# Microcontroller_board_Photodiode_plate.net
KiCad netlist of a schematic drawn in EasyEDA
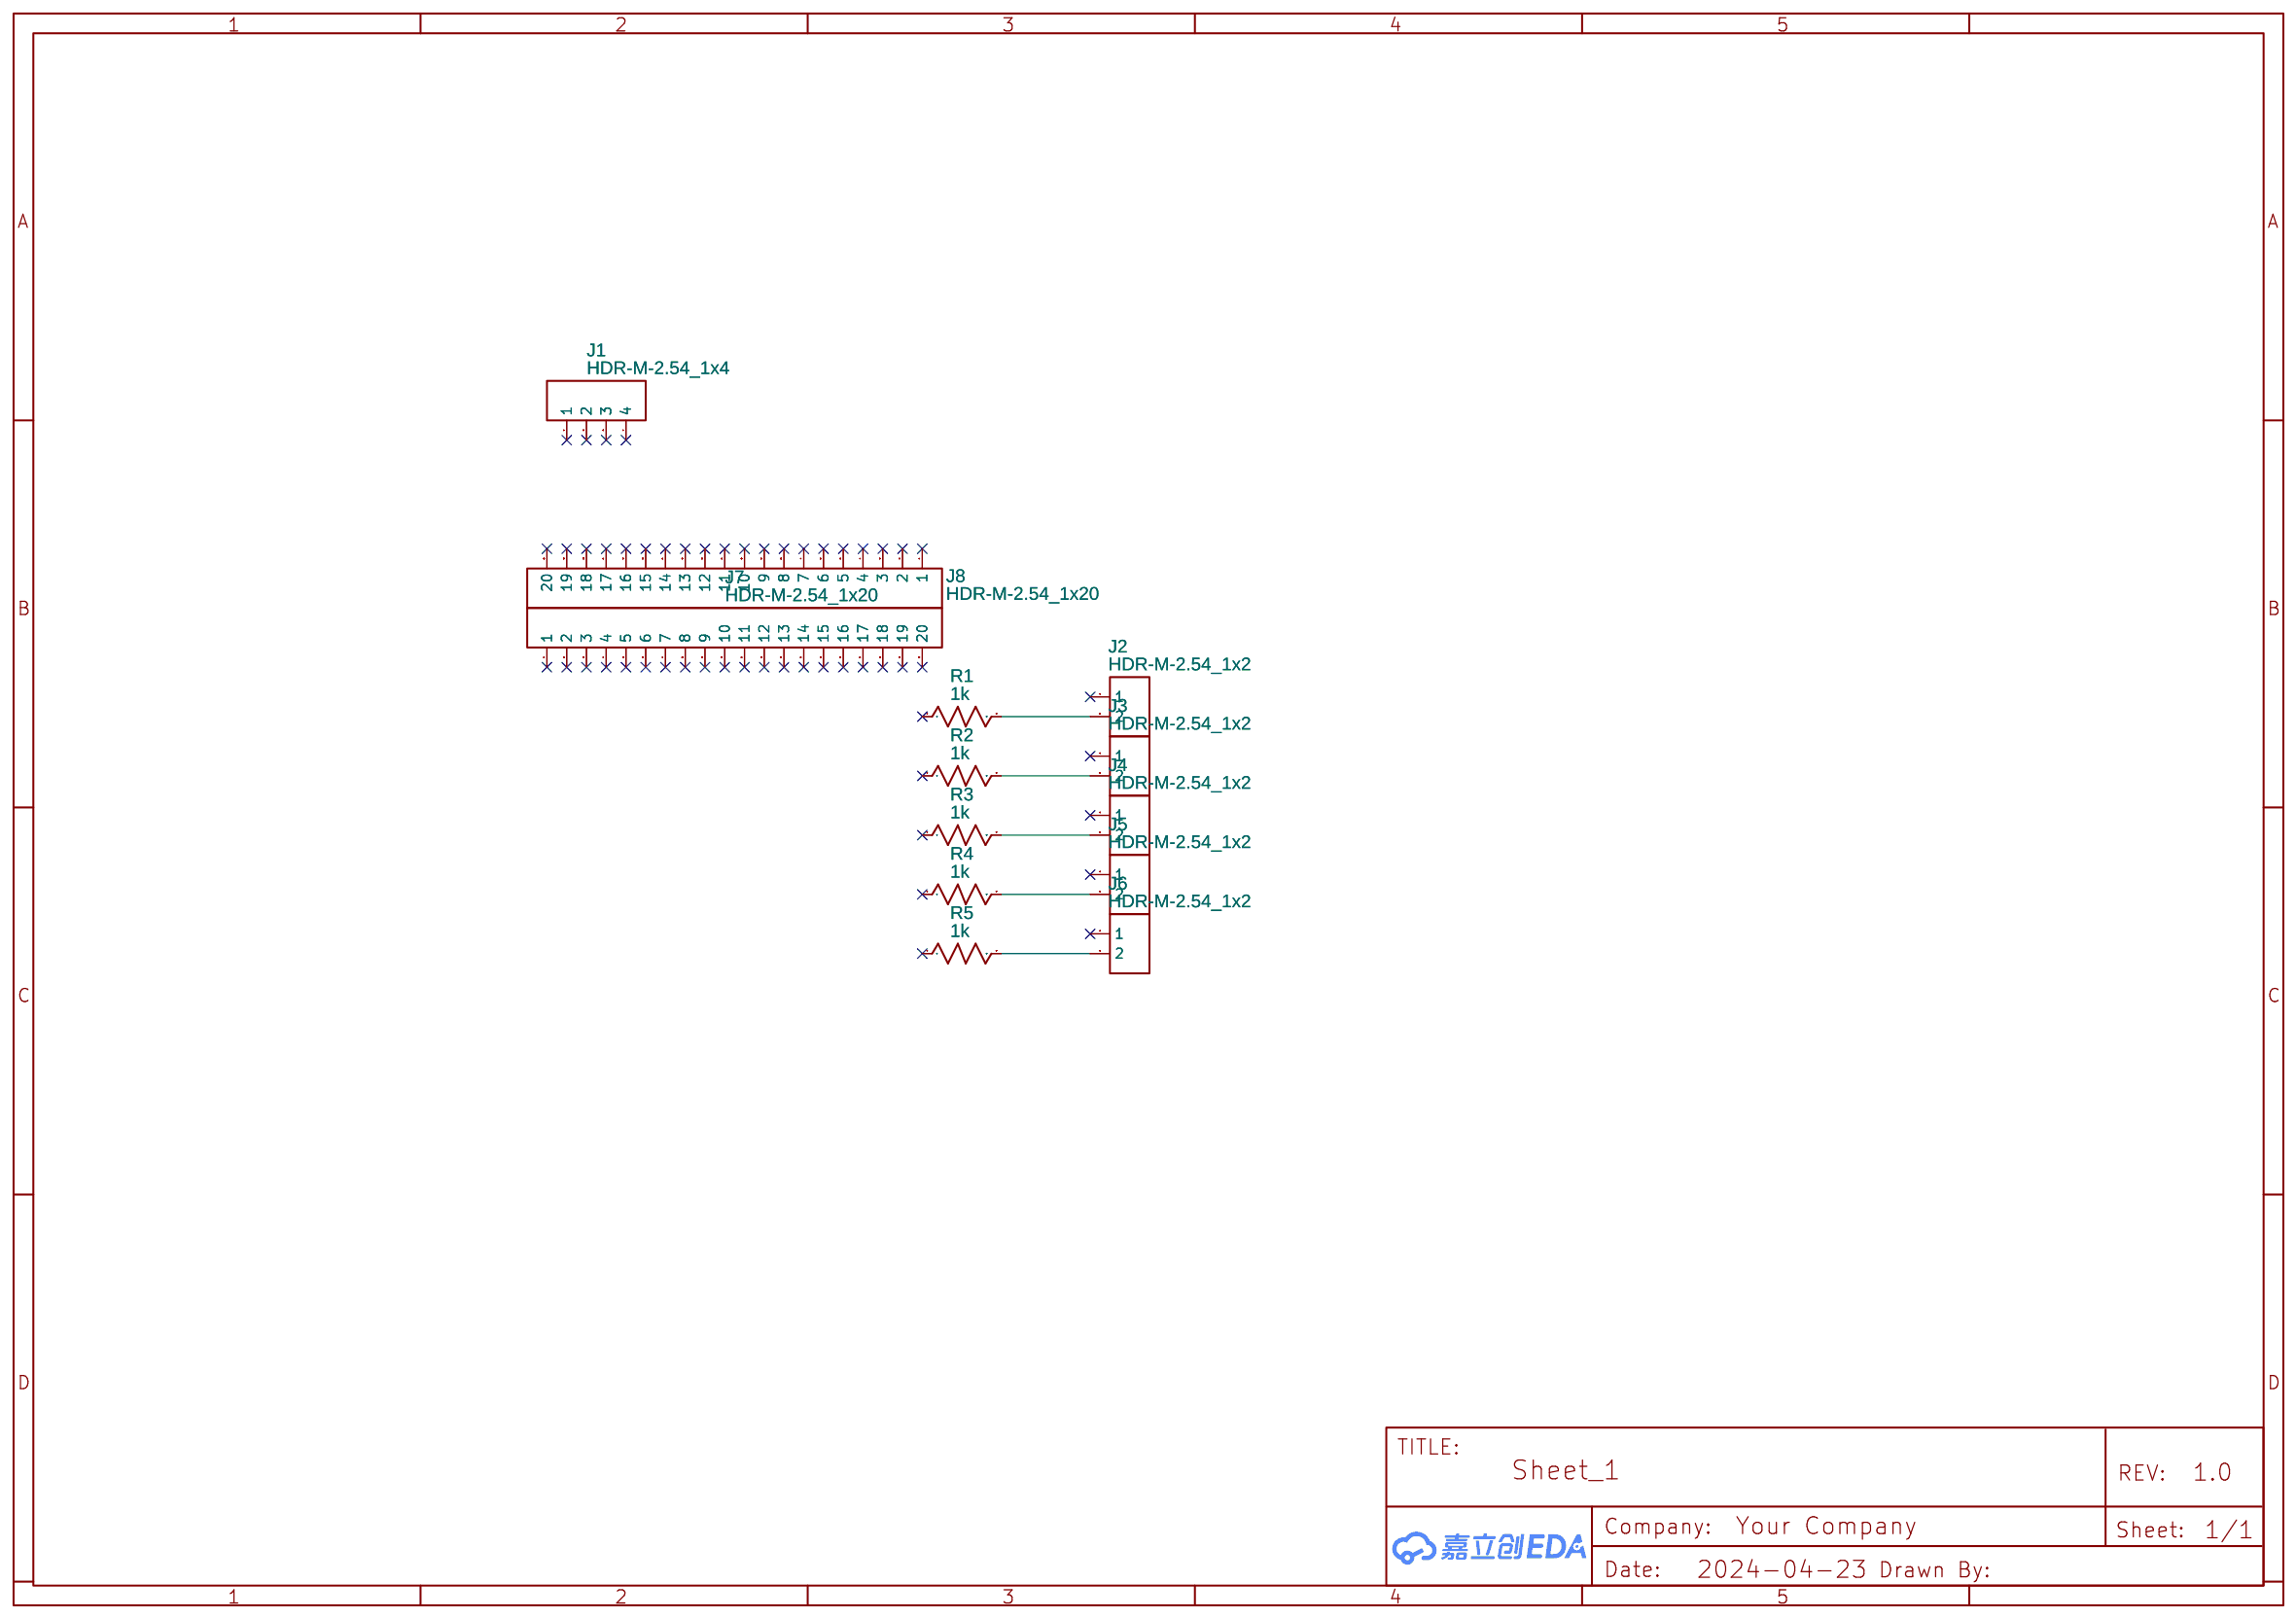
[diagram p0: schematic sheet]

(export (version "E")
  (design (tool "Eeschema 10.0.6"))
  (components
    (comp (ref "J1")
      (value "HDR-M-2.54_1x4")
      (fields (field (name "BOM_Supplier Part") "C124378"))
      (libsource (lib "") (part "HDR-M-2.54_1x4"))
    )
    (comp (ref "J2")
      (value "HDR-M-2.54_1x2")
      (fields (field (name "BOM_Supplier Part") "C124375"))
      (libsource (lib "") (part "HDR-M-2.54_1x2"))
    )
    (comp (ref "J3")
      (value "HDR-M-2.54_1x2")
      (fields (field (name "BOM_Supplier Part") "C124375"))
      (libsource (lib "") (part "HDR-M-2.54_1x2"))
    )
    (comp (ref "J4")
      (value "HDR-M-2.54_1x2")
      (fields (field (name "BOM_Supplier Part") "C124375"))
      (libsource (lib "") (part "HDR-M-2.54_1x2"))
    )
    (comp (ref "J5")
      (value "HDR-M-2.54_1x2")
      (fields (field (name "BOM_Supplier Part") "C124375"))
      (libsource (lib "") (part "HDR-M-2.54_1x2"))
    )
    (comp (ref "J6")
      (value "HDR-M-2.54_1x2")
      (fields (field (name "BOM_Supplier Part") "C124375"))
      (libsource (lib "") (part "HDR-M-2.54_1x2"))
    )
    (comp (ref "J7")
      (value "HDR-M-2.54_1x20")
      (fields (field (name "BOM_Supplier Part") "C50981"))
      (libsource (lib "") (part "HDR-M-2.54_1x20"))
    )
    (comp (ref "J8")
      (value "HDR-M-2.54_1x20")
      (fields (field (name "BOM_Supplier Part") "C50981"))
      (libsource (lib "") (part "HDR-M-2.54_1x20_1"))
    )
    (comp (ref "R1") (value "1k") (libsource (lib "") (part "R_AXIAL-0.3_US")))
    (comp (ref "R2") (value "1k") (libsource (lib "") (part "R_AXIAL-0.3_US")))
    (comp (ref "R3") (value "1k") (libsource (lib "") (part "R_AXIAL-0.3_US")))
    (comp (ref "R4") (value "1k") (libsource (lib "") (part "R_AXIAL-0.3_US")))
    (comp (ref "R5") (value "1k") (libsource (lib "") (part "R_AXIAL-0.3_US")))
  )
  (nets
    (net (code "1") (name "Net-(J2-Pad2)") (class "Default")
      (node (ref "J2") (pin "2") (pinfunction "2_2") (pintype "unspecified"))
      (node (ref "R1") (pin "2") (pinfunction "2_2") (pintype "unspecified"))
    )
    (net (code "2") (name "Net-(J3-Pad2)") (class "Default")
      (node (ref "J3") (pin "2") (pinfunction "2_2") (pintype "unspecified"))
      (node (ref "R2") (pin "2") (pinfunction "2_2") (pintype "unspecified"))
    )
    (net (code "3") (name "Net-(J4-Pad2)") (class "Default")
      (node (ref "J4") (pin "2") (pinfunction "2_2") (pintype "unspecified"))
      (node (ref "R3") (pin "2") (pinfunction "2_2") (pintype "unspecified"))
    )
    (net (code "4") (name "Net-(J5-Pad2)") (class "Default")
      (node (ref "J5") (pin "2") (pinfunction "2_2") (pintype "unspecified"))
      (node (ref "R4") (pin "2") (pinfunction "2_2") (pintype "unspecified"))
    )
    (net (code "5") (name "Net-(J6-Pad2)") (class "Default")
      (node (ref "J6") (pin "2") (pinfunction "2_2") (pintype "unspecified"))
      (node (ref "R5") (pin "2") (pinfunction "2_2") (pintype "unspecified"))
    )
    (net (code "6") (name "unconnected-(J1-Pad1)") (class "Default")
      (node (ref "J1") (pin "1") (pinfunction "1_1") (pintype "unspecified+no_connect"))
    )
    (net (code "7") (name "unconnected-(J1-Pad2)") (class "Default")
      (node (ref "J1") (pin "2") (pinfunction "2_2") (pintype "unspecified+no_connect"))
    )
    (net (code "8") (name "unconnected-(J1-Pad3)") (class "Default")
      (node (ref "J1") (pin "3") (pinfunction "3_3") (pintype "unspecified+no_connect"))
    )
    (net (code "9") (name "unconnected-(J1-Pad4)") (class "Default")
      (node (ref "J1") (pin "4") (pinfunction "4_4") (pintype "unspecified+no_connect"))
    )
    (net (code "10") (name "unconnected-(J2-Pad1)") (class "Default")
      (node (ref "J2") (pin "1") (pinfunction "1_1") (pintype "unspecified+no_connect"))
    )
    (net (code "11") (name "unconnected-(J3-Pad1)") (class "Default")
      (node (ref "J3") (pin "1") (pinfunction "1_1") (pintype "unspecified+no_connect"))
    )
    (net (code "12") (name "unconnected-(J4-Pad1)") (class "Default")
      (node (ref "J4") (pin "1") (pinfunction "1_1") (pintype "unspecified+no_connect"))
    )
    (net (code "13") (name "unconnected-(J5-Pad1)") (class "Default")
      (node (ref "J5") (pin "1") (pinfunction "1_1") (pintype "unspecified+no_connect"))
    )
    (net (code "14") (name "unconnected-(J6-Pad1)") (class "Default")
      (node (ref "J6") (pin "1") (pinfunction "1_1") (pintype "unspecified+no_connect"))
    )
    (net (code "15") (name "unconnected-(J7-Pad1)") (class "Default")
      (node (ref "J7") (pin "1") (pinfunction "1_1") (pintype "unspecified+no_connect"))
    )
    (net (code "16") (name "unconnected-(J7-Pad2)") (class "Default")
      (node (ref "J7") (pin "2") (pinfunction "2_2") (pintype "unspecified+no_connect"))
    )
    (net (code "17") (name "unconnected-(J7-Pad3)") (class "Default")
      (node (ref "J7") (pin "3") (pinfunction "3_3") (pintype "unspecified+no_connect"))
    )
    (net (code "18") (name "unconnected-(J7-Pad4)") (class "Default")
      (node (ref "J7") (pin "4") (pinfunction "4_4") (pintype "unspecified+no_connect"))
    )
    (net (code "19") (name "unconnected-(J7-Pad5)") (class "Default")
      (node (ref "J7") (pin "5") (pinfunction "5_5") (pintype "unspecified+no_connect"))
    )
    (net (code "20") (name "unconnected-(J7-Pad6)") (class "Default")
      (node (ref "J7") (pin "6") (pinfunction "6_6") (pintype "unspecified+no_connect"))
    )
    (net (code "21") (name "unconnected-(J7-Pad7)") (class "Default")
      (node (ref "J7") (pin "7") (pinfunction "7_7") (pintype "unspecified+no_connect"))
    )
    (net (code "22") (name "unconnected-(J7-Pad8)") (class "Default")
      (node (ref "J7") (pin "8") (pinfunction "8_8") (pintype "unspecified+no_connect"))
    )
    (net (code "23") (name "unconnected-(J7-Pad9)") (class "Default")
      (node (ref "J7") (pin "9") (pinfunction "9_9") (pintype "unspecified+no_connect"))
    )
    (net (code "24") (name "unconnected-(J7-Pad10)") (class "Default")
      (node (ref "J7") (pin "10") (pinfunction "10_10") (pintype "unspecified+no_connect"))
    )
    (net (code "25") (name "unconnected-(J7-Pad11)") (class "Default")
      (node (ref "J7") (pin "11") (pinfunction "11_11") (pintype "unspecified+no_connect"))
    )
    (net (code "26") (name "unconnected-(J7-Pad12)") (class "Default")
      (node (ref "J7") (pin "12") (pinfunction "12_12") (pintype "unspecified+no_connect"))
    )
    (net (code "27") (name "unconnected-(J7-Pad13)") (class "Default")
      (node (ref "J7") (pin "13") (pinfunction "13_13") (pintype "unspecified+no_connect"))
    )
    (net (code "28") (name "unconnected-(J7-Pad14)") (class "Default")
      (node (ref "J7") (pin "14") (pinfunction "14_14") (pintype "unspecified+no_connect"))
    )
    (net (code "29") (name "unconnected-(J7-Pad15)") (class "Default")
      (node (ref "J7") (pin "15") (pinfunction "15_15") (pintype "unspecified+no_connect"))
    )
    (net (code "30") (name "unconnected-(J7-Pad16)") (class "Default")
      (node (ref "J7") (pin "16") (pinfunction "16_16") (pintype "unspecified+no_connect"))
    )
    (net (code "31") (name "unconnected-(J7-Pad17)") (class "Default")
      (node (ref "J7") (pin "17") (pinfunction "17_17") (pintype "unspecified+no_connect"))
    )
    (net (code "32") (name "unconnected-(J7-Pad18)") (class "Default")
      (node (ref "J7") (pin "18") (pinfunction "18_18") (pintype "unspecified+no_connect"))
    )
    (net (code "33") (name "unconnected-(J7-Pad19)") (class "Default")
      (node (ref "J7") (pin "19") (pinfunction "19_19") (pintype "unspecified+no_connect"))
    )
    (net (code "34") (name "unconnected-(J7-Pad20)") (class "Default")
      (node (ref "J7") (pin "20") (pinfunction "20_20") (pintype "unspecified+no_connect"))
    )
    (net (code "35") (name "unconnected-(J8-Pad1)") (class "Default")
      (node (ref "J8") (pin "1") (pinfunction "1_1") (pintype "unspecified+no_connect"))
    )
    (net (code "36") (name "unconnected-(J8-Pad2)") (class "Default")
      (node (ref "J8") (pin "2") (pinfunction "2_2") (pintype "unspecified+no_connect"))
    )
    (net (code "37") (name "unconnected-(J8-Pad3)") (class "Default")
      (node (ref "J8") (pin "3") (pinfunction "3_3") (pintype "unspecified+no_connect"))
    )
    (net (code "38") (name "unconnected-(J8-Pad4)") (class "Default")
      (node (ref "J8") (pin "4") (pinfunction "4_4") (pintype "unspecified+no_connect"))
    )
    (net (code "39") (name "unconnected-(J8-Pad5)") (class "Default")
      (node (ref "J8") (pin "5") (pinfunction "5_5") (pintype "unspecified+no_connect"))
    )
    (net (code "40") (name "unconnected-(J8-Pad6)") (class "Default")
      (node (ref "J8") (pin "6") (pinfunction "6_6") (pintype "unspecified+no_connect"))
    )
    (net (code "41") (name "unconnected-(J8-Pad7)") (class "Default")
      (node (ref "J8") (pin "7") (pinfunction "7_7") (pintype "unspecified+no_connect"))
    )
    (net (code "42") (name "unconnected-(J8-Pad8)") (class "Default")
      (node (ref "J8") (pin "8") (pinfunction "8_8") (pintype "unspecified+no_connect"))
    )
    (net (code "43") (name "unconnected-(J8-Pad9)") (class "Default")
      (node (ref "J8") (pin "9") (pinfunction "9_9") (pintype "unspecified+no_connect"))
    )
    (net (code "44") (name "unconnected-(J8-Pad10)") (class "Default")
      (node (ref "J8") (pin "10") (pinfunction "10_10") (pintype "unspecified+no_connect"))
    )
    (net (code "45") (name "unconnected-(J8-Pad11)") (class "Default")
      (node (ref "J8") (pin "11") (pinfunction "11_11") (pintype "unspecified+no_connect"))
    )
    (net (code "46") (name "unconnected-(J8-Pad12)") (class "Default")
      (node (ref "J8") (pin "12") (pinfunction "12_12") (pintype "unspecified+no_connect"))
    )
    (net (code "47") (name "unconnected-(J8-Pad13)") (class "Default")
      (node (ref "J8") (pin "13") (pinfunction "13_13") (pintype "unspecified+no_connect"))
    )
    (net (code "48") (name "unconnected-(J8-Pad14)") (class "Default")
      (node (ref "J8") (pin "14") (pinfunction "14_14") (pintype "unspecified+no_connect"))
    )
    (net (code "49") (name "unconnected-(J8-Pad15)") (class "Default")
      (node (ref "J8") (pin "15") (pinfunction "15_15") (pintype "unspecified+no_connect"))
    )
    (net (code "50") (name "unconnected-(J8-Pad16)") (class "Default")
      (node (ref "J8") (pin "16") (pinfunction "16_16") (pintype "unspecified+no_connect"))
    )
    (net (code "51") (name "unconnected-(J8-Pad17)") (class "Default")
      (node (ref "J8") (pin "17") (pinfunction "17_17") (pintype "unspecified+no_connect"))
    )
    (net (code "52") (name "unconnected-(J8-Pad18)") (class "Default")
      (node (ref "J8") (pin "18") (pinfunction "18_18") (pintype "unspecified+no_connect"))
    )
    (net (code "53") (name "unconnected-(J8-Pad19)") (class "Default")
      (node (ref "J8") (pin "19") (pinfunction "19_19") (pintype "unspecified+no_connect"))
    )
    (net (code "54") (name "unconnected-(J8-Pad20)") (class "Default")
      (node (ref "J8") (pin "20") (pinfunction "20_20") (pintype "unspecified+no_connect"))
    )
    (net (code "55") (name "unconnected-(R1-Pad1)") (class "Default")
      (node (ref "R1") (pin "1") (pinfunction "1_1") (pintype "unspecified+no_connect"))
    )
    (net (code "56") (name "unconnected-(R2-Pad1)") (class "Default")
      (node (ref "R2") (pin "1") (pinfunction "1_1") (pintype "unspecified+no_connect"))
    )
    (net (code "57") (name "unconnected-(R3-Pad1)") (class "Default")
      (node (ref "R3") (pin "1") (pinfunction "1_1") (pintype "unspecified+no_connect"))
    )
    (net (code "58") (name "unconnected-(R4-Pad1)") (class "Default")
      (node (ref "R4") (pin "1") (pinfunction "1_1") (pintype "unspecified+no_connect"))
    )
    (net (code "59") (name "unconnected-(R5-Pad1)") (class "Default")
      (node (ref "R5") (pin "1") (pinfunction "1_1") (pintype "unspecified+no_connect"))
    )
  )
)
